# Project2SCH.net
KiCad netlist of a schematic drawn in Altium Designer
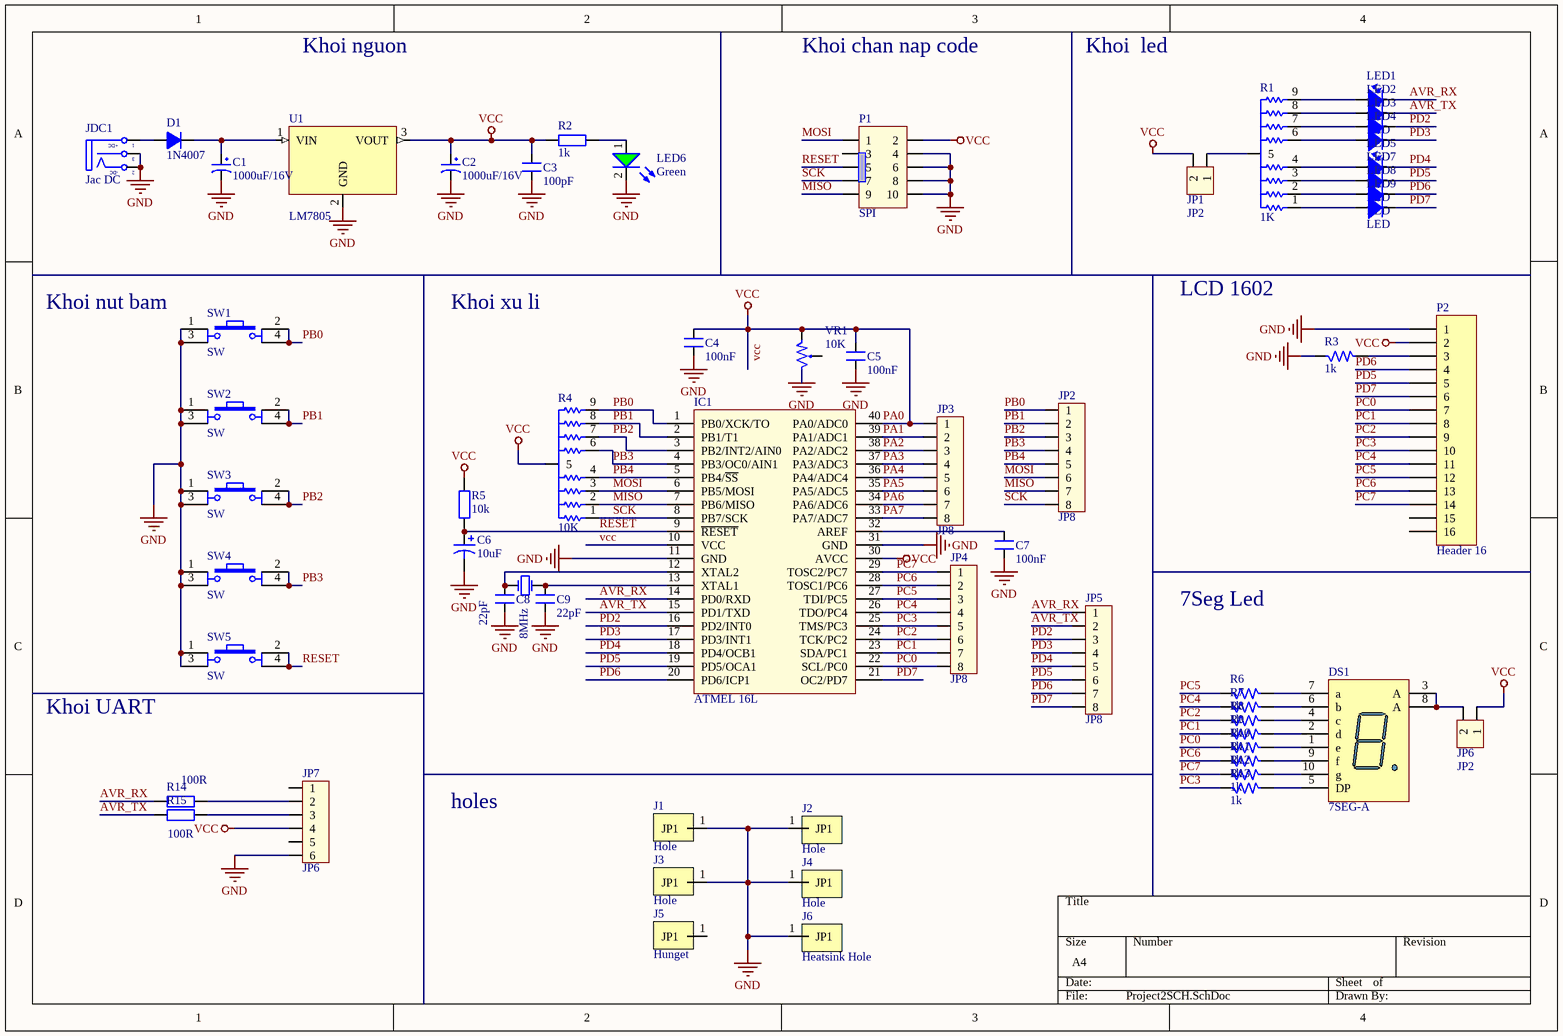
[diagram p0: Project2SCH.SchDoc]

(export (version "E")
  (design (tool "Eeschema 10.0.6"))
  (components
    (comp (ref "C1")
      (value "1000uF/16V")
      (footprint "CP1.5/3.4")
      (description "Cap 1000uF/16V - 220uF/50V")
      (libsource (lib "Cty1") (part "CP4"))
    )
    (comp (ref "C2")
      (value "1000uF/16V")
      (footprint "CP1.5/3.4")
      (description "Cap 1000uF/16V - 220uF/50V")
      (libsource (lib "Cty1") (part "CP4"))
    )
    (comp (ref "C3")
      (value "100pF")
      (footprint "CN1")
      (description "Cap np  1pF - 472pF")
      (libsource (lib "SCH_Lib_Devzone") (part "CN1"))
    )
    (comp (ref "C4")
      (value "100nF")
      (footprint "CN1")
      (description "Cap np  1pF - 472pF")
      (libsource (lib "Cty1") (part "CN1"))
    )
    (comp (ref "C5")
      (value "100nF")
      (footprint "CN1")
      (description "Cap np  1pF - 472pF")
      (libsource (lib "Cty1") (part "CN1"))
    )
    (comp (ref "C6")
      (value "10uF")
      (footprint "C5mm")
      (description "Polarized Capacitor (Axial)")
      (fields (field (name "PUBLISHER") "Altium Limited"))
      (libsource (lib "Schematic") (part "Cap Pol 5mm"))
    )
    (comp (ref "C7")
      (value "100nF")
      (footprint "CN1")
      (description "Cap np  1pF - 472pF")
      (libsource (lib "SCH_Lib_Devzone") (part "CN1"))
    )
    (comp (ref "C8")
      (value "22pF")
      (footprint "CN1")
      (description "Cap np  1pF - 472pF")
      (libsource (lib "Cty1") (part "CN1"))
    )
    (comp (ref "C9")
      (value "22pF")
      (footprint "CN1")
      (description "Cap np  1pF - 472pF")
      (libsource (lib "Cty1") (part "CN1"))
    )
    (comp (ref "D1")
      (value "1N4007")
      (footprint "D2A")
      (description "Diode 1A")
      (libsource (lib "Cty1") (part "D1A"))
    )
    (comp (ref "DS1")
      (value "7SEG-A")
      (footprint "LED7SEG")
      (description "14.2 mm General Purpose Blue 7-Segment Display: CA, RH DP, Gray Surface")
      (fields (field (name "PUBLISHER") "Altium Limited"))
      (libsource (lib "Schematic") (part "LED7SEG-A"))
    )
    (comp (ref "IC1")
      (value "ATMEL 16L")
      (footprint "DIP40/W0.6")
      (description "8-Bit AVR Microcontroller with 16K Bytes of In-System Programmable Flash Memory")
      (libsource (lib "SCH_Lib_Devzone") (part "Atmega16L"))
    )
    (comp (ref "J1")
      (value "Hole")
      (footprint "JP1")
      (description "JP1")
      (libsource (lib "SCH_Lib_Devzone") (part "JP1"))
    )
    (comp (ref "J2") (value "Hole") (footprint "JP1") (description "JP1") (libsource (lib "") (part "JP1_1")))
    (comp (ref "J3")
      (value "Hole")
      (footprint "JP1")
      (description "JP1")
      (libsource (lib "SCH_Lib_Devzone") (part "JP1"))
    )
    (comp (ref "J4") (value "Hole") (footprint "JP1") (description "JP1") (libsource (lib "") (part "JP1_1")))
    (comp (ref "J5")
      (value "Hunget")
      (footprint "JP1")
      (description "JP1")
      (libsource (lib "SCH_Lib_Devzone") (part "JP1"))
    )
    (comp (ref "J6")
      (value "Heatsink Hole")
      (footprint "JP1")
      (description "JP1")
      (libsource (lib "") (part "JP1_1"))
    )
    (comp (ref "JDC1")
      (value "Jac DC")
      (footprint "DC-IN")
      (description "Jac DC input")
      (libsource (lib "Cty1") (part "DCIN"))
    )
    (comp (ref "JP1")
      (value "JP2")
      (footprint "CON2")
      (description "Connector 2")
      (libsource (lib "SCH_MyLib_0") (part "Con2"))
    )
    (comp (ref "JP2")
      (value "JP8")
      (footprint "CON8")
      (description "Connector 8")
      (libsource (lib "VioletofSun") (part "Con8"))
    )
    (comp (ref "JP3")
      (value "JP8")
      (footprint "CON8")
      (description "Connector 8")
      (libsource (lib "VioletofSun") (part "Con8"))
    )
    (comp (ref "JP4")
      (value "JP8")
      (footprint "CON8")
      (description "Connector 8")
      (libsource (lib "VioletofSun") (part "Con8"))
    )
    (comp (ref "JP5")
      (value "JP8")
      (footprint "CON8")
      (description "Connector 8")
      (libsource (lib "VioletofSun") (part "Con8"))
    )
    (comp (ref "JP6")
      (value "JP2")
      (footprint "CON2")
      (description "Connector 2")
      (libsource (lib "SCH_MyLib_0") (part "Con2"))
    )
    (comp (ref "JP7")
      (value "JP6")
      (footprint "CON6")
      (description "Connector 6")
      (libsource (lib "syhaunguyen") (part "Con6"))
    )
    (comp (ref "LED1")
      (value "LED")
      (footprint "LED-V")
      (description "LED Single colour Green and Red")
      (libsource (lib "SCH_Lib_Devzone") (part "LED"))
    )
    (comp (ref "LED2")
      (value "LED")
      (footprint "LED-V")
      (description "LED Single colour Green and Red")
      (libsource (lib "SCH_Lib_Devzone") (part "LED"))
    )
    (comp (ref "LED3")
      (value "LED")
      (footprint "LED-V")
      (description "LED Single colour Green and Red")
      (libsource (lib "SCH_Lib_Devzone") (part "LED"))
    )
    (comp (ref "LED4")
      (value "LED")
      (footprint "LED-V")
      (description "LED Single colour Green and Red")
      (libsource (lib "SCH_Lib_Devzone") (part "LED"))
    )
    (comp (ref "LED5")
      (value "LED")
      (footprint "LED-V")
      (description "LED Single colour Green and Red")
      (libsource (lib "SCH_Lib_Devzone") (part "LED"))
    )
    (comp (ref "LED6")
      (value "Green")
      (footprint "LED5G")
      (description "LED Green 5mm")
      (fields (field (name "Comment") "LED_G_5"))
      (libsource (lib "SCH_MyLib_0") (part "LED_GREEN_5MM"))
    )
    (comp (ref "LED7")
      (value "LED")
      (footprint "LED-V")
      (description "LED Single colour Green and Red")
      (libsource (lib "SCH_Lib_Devzone") (part "LED"))
    )
    (comp (ref "LED8")
      (value "LED")
      (footprint "LED-V")
      (description "LED Single colour Green and Red")
      (libsource (lib "SCH_Lib_Devzone") (part "LED"))
    )
    (comp (ref "LED9")
      (value "LED")
      (footprint "LED-V")
      (description "LED Single colour Green and Red")
      (libsource (lib "SCH_Lib_Devzone") (part "LED"))
    )
    (comp (ref "P1")
      (value "SPI")
      (footprint "IDE_2X5")
      (description "Header 5x2")
      (libsource (lib "SCH_Lib_Devzone") (part "IDE 5x2"))
    )
    (comp (ref "P2")
      (value "Header 16")
      (footprint "HDR1X16")
      (description "Header, 16-Pin")
      (fields (field (name "PUBLISHER") "Altium Limited"))
      (libsource (lib "Devzone_SCHLib") (part "Header 16"))
    )
    (comp (ref "R1")
      (value "1K")
      (footprint "VioletofSun:RN8")
      (description "Resistor Pack 4x2")
      (libsource (lib "VioletofSun") (part "RKC8LD"))
    )
    (comp (ref "R2")
      (value "1k")
      (footprint "R1/4W")
      (description "Resistor 1/4W")
      (libsource (lib "SCH_Lib_Devzone") (part "R1/4W"))
    )
    (comp (ref "R3")
      (value "1k")
      (footprint "R1/6W")
      (description "Resistor 1/4W")
      (libsource (lib "Cty1") (part "Res"))
    )
    (comp (ref "R4")
      (value "10K")
      (footprint "VioletofSun:RN8")
      (description "Resistor Pack 4x2")
      (libsource (lib "VioletofSun") (part "RKC8LD"))
    )
    (comp (ref "R5")
      (value "10k")
      (footprint "R1/4W")
      (description "Resistor 1/4W")
      (libsource (lib "Devzone_SCHLib") (part "R1/4W"))
    )
    (comp (ref "R6")
      (value "1k")
      (footprint "R1/6W")
      (description "Resistor 1/4W")
      (libsource (lib "Cty1") (part "Res"))
    )
    (comp (ref "R7")
      (value "1k")
      (footprint "R1/6W")
      (description "Resistor 1/4W")
      (libsource (lib "Cty1") (part "Res"))
    )
    (comp (ref "R8")
      (value "1k")
      (footprint "R1/6W")
      (description "Resistor 1/4W")
      (libsource (lib "Cty1") (part "Res"))
    )
    (comp (ref "R9")
      (value "1k")
      (footprint "R1/6W")
      (description "Resistor 1/4W")
      (libsource (lib "Cty1") (part "Res"))
    )
    (comp (ref "R10")
      (value "1k")
      (footprint "R1/6W")
      (description "Resistor 1/4W")
      (libsource (lib "Cty1") (part "Res"))
    )
    (comp (ref "R11")
      (value "1k")
      (footprint "R1/6W")
      (description "Resistor 1/4W")
      (libsource (lib "Cty1") (part "Res"))
    )
    (comp (ref "R12")
      (value "1k")
      (footprint "R1/6W")
      (description "Resistor 1/4W")
      (libsource (lib "Cty1") (part "Res"))
    )
    (comp (ref "R13")
      (value "1k")
      (footprint "R1/6W")
      (description "Resistor 1/4W")
      (libsource (lib "Cty1") (part "Res"))
    )
    (comp (ref "R14")
      (value "100R")
      (footprint "R1/4W")
      (description "Resistor 1/4W")
      (libsource (lib "Devzone_SCHLib") (part "R1/4W"))
    )
    (comp (ref "R15")
      (value "100R")
      (footprint "R1/4W")
      (description "Resistor 1/4W")
      (libsource (lib "Devzone_SCHLib") (part "R1/4W"))
    )
    (comp (ref "SW1")
      (value "SW")
      (footprint "SW-4P-S")
      (description "Switch button 4 pin")
      (libsource (lib "Cty1") (part "SW4"))
    )
    (comp (ref "SW2")
      (value "SW")
      (footprint "SW-4P-S")
      (description "Switch button 4 pin")
      (libsource (lib "Cty1") (part "SW4"))
    )
    (comp (ref "SW3")
      (value "SW")
      (footprint "SW-4P-S")
      (description "Switch button 4 pin")
      (libsource (lib "Cty1") (part "SW4"))
    )
    (comp (ref "SW4")
      (value "SW")
      (footprint "SW-4P-S")
      (description "Switch button 4 pin")
      (libsource (lib "Cty1") (part "SW4"))
    )
    (comp (ref "SW5")
      (value "SW")
      (footprint "SW-4P-S")
      (description "Switch button 4 pin")
      (libsource (lib "Cty1") (part "SW4"))
    )
    (comp (ref "U1")
      (value "LM7805")
      (footprint "QTO-220H3")
      (description "TO-220")
      (libsource (lib "Cty1") (part "LM7805"))
    )
    (comp (ref "VR1")
      (value "10K")
      (footprint "VioletofSun:VR")
      (description "Var Resistor")
      (libsource (lib "VioletofSun") (part "VR1"))
    )
    (comp (ref "Y1")
      (value "8MHz")
      (footprint "XT2")
      (description "Crystal Oscillator")
      (fields (field (name "PUBLISHER") "Altium Limited"))
      (libsource (lib "Devzone_SCHLib") (part "Crystal"))
    )
  )
  (nets
    (net (code "1") (name "/AVR_RX") (class "Default")
      (node (ref "IC1") (pin "14") (pinfunction "PD0/RXD_14") (pintype "passive"))
      (node (ref "JP5") (pin "1") (pinfunction "1_1") (pintype "passive"))
      (node (ref "LED1") (pin "2") (pinfunction "2_2") (pintype "passive"))
      (node (ref "R14") (pin "1") (pinfunction "1_1") (pintype "passive"))
    )
    (net (code "2") (name "/AVR_TX") (class "Default")
      (node (ref "IC1") (pin "15") (pinfunction "PD1/TXD_15") (pintype "passive"))
      (node (ref "JP5") (pin "2") (pinfunction "2_2") (pintype "passive"))
      (node (ref "LED2") (pin "2") (pinfunction "2_2") (pintype "passive"))
      (node (ref "R15") (pin "1") (pinfunction "1_1") (pintype "passive"))
    )
    (net (code "3") (name "/MISO") (class "Default")
      (node (ref "IC1") (pin "7") (pinfunction "PB6/MISO_7") (pintype "passive"))
      (node (ref "JP2") (pin "7") (pinfunction "7_7") (pintype "passive"))
      (node (ref "P1") (pin "9") (pinfunction "9_9") (pintype "passive"))
      (node (ref "R4") (pin "2") (pinfunction "2_2") (pintype "passive"))
    )
    (net (code "4") (name "/MOSI") (class "Default")
      (node (ref "IC1") (pin "6") (pinfunction "PB5/MOSI_6") (pintype "passive"))
      (node (ref "JP2") (pin "6") (pinfunction "6_6") (pintype "passive"))
      (node (ref "P1") (pin "1") (pinfunction "1_1") (pintype "passive"))
      (node (ref "R4") (pin "3") (pinfunction "3_3") (pintype "passive"))
    )
    (net (code "5") (name "/PA1") (class "Default")
      (node (ref "IC1") (pin "39") (pinfunction "PA1/ADC1_39") (pintype "passive"))
      (node (ref "JP3") (pin "2") (pinfunction "2_2") (pintype "passive"))
    )
    (net (code "6") (name "/PA2") (class "Default")
      (node (ref "IC1") (pin "38") (pinfunction "PA2/ADC2_38") (pintype "passive"))
      (node (ref "JP3") (pin "3") (pinfunction "3_3") (pintype "passive"))
    )
    (net (code "7") (name "/PA3") (class "Default")
      (node (ref "IC1") (pin "37") (pinfunction "PA3/ADC3_37") (pintype "passive"))
      (node (ref "JP3") (pin "4") (pinfunction "4_4") (pintype "passive"))
    )
    (net (code "8") (name "/PA4") (class "Default")
      (node (ref "IC1") (pin "36") (pinfunction "PA4/ADC4_36") (pintype "passive"))
      (node (ref "JP3") (pin "5") (pinfunction "5_5") (pintype "passive"))
    )
    (net (code "9") (name "/PA5") (class "Default")
      (node (ref "IC1") (pin "35") (pinfunction "PA5/ADC5_35") (pintype "passive"))
      (node (ref "JP3") (pin "6") (pinfunction "6_6") (pintype "passive"))
    )
    (net (code "10") (name "/PA6") (class "Default")
      (node (ref "IC1") (pin "34") (pinfunction "PA6/ADC6_34") (pintype "passive"))
      (node (ref "JP3") (pin "7") (pinfunction "7_7") (pintype "passive"))
    )
    (net (code "11") (name "/PA7") (class "Default")
      (node (ref "IC1") (pin "33") (pinfunction "PA7/ADC7_33") (pintype "passive"))
      (node (ref "JP3") (pin "8") (pinfunction "8_8") (pintype "passive"))
    )
    (net (code "12") (name "/PB0") (class "Default")
      (node (ref "IC1") (pin "1") (pinfunction "PB0/XCK/TO_1") (pintype "passive"))
      (node (ref "JP2") (pin "1") (pinfunction "1_1") (pintype "passive"))
      (node (ref "R4") (pin "9") (pinfunction "9_9") (pintype "passive"))
      (node (ref "SW1") (pin "2") (pintype "passive"))
      (node (ref "SW1") (pin "4") (pintype "passive"))
    )
    (net (code "13") (name "/PB1") (class "Default")
      (node (ref "IC1") (pin "2") (pinfunction "PB1/T1_2") (pintype "passive"))
      (node (ref "JP2") (pin "2") (pinfunction "2_2") (pintype "passive"))
      (node (ref "R4") (pin "8") (pinfunction "8_8") (pintype "passive"))
      (node (ref "SW2") (pin "2") (pintype "passive"))
      (node (ref "SW2") (pin "4") (pintype "passive"))
    )
    (net (code "14") (name "/PB2") (class "Default")
      (node (ref "IC1") (pin "3") (pinfunction "PB2/INT2/AIN0_3") (pintype "passive"))
      (node (ref "JP2") (pin "3") (pinfunction "3_3") (pintype "passive"))
      (node (ref "R4") (pin "7") (pinfunction "7_7") (pintype "passive"))
      (node (ref "SW3") (pin "2") (pintype "passive"))
      (node (ref "SW3") (pin "4") (pintype "passive"))
    )
    (net (code "15") (name "/PB3") (class "Default")
      (node (ref "IC1") (pin "4") (pinfunction "PB3/OC0/AIN1_4") (pintype "passive"))
      (node (ref "JP2") (pin "4") (pinfunction "4_4") (pintype "passive"))
      (node (ref "R4") (pin "6") (pinfunction "6_6") (pintype "passive"))
      (node (ref "SW4") (pin "2") (pintype "passive"))
      (node (ref "SW4") (pin "4") (pintype "passive"))
    )
    (net (code "16") (name "/PB4") (class "Default")
      (node (ref "IC1") (pin "5") (pinfunction "PB4/~{SS}_5") (pintype "passive"))
      (node (ref "JP2") (pin "5") (pinfunction "5_5") (pintype "passive"))
      (node (ref "R4") (pin "4") (pinfunction "4_4") (pintype "passive"))
    )
    (net (code "17") (name "/PC0") (class "Default")
      (node (ref "IC1") (pin "22") (pinfunction "SCL/PC0_22") (pintype "passive"))
      (node (ref "JP4") (pin "8") (pinfunction "8_8") (pintype "passive"))
      (node (ref "P2") (pin "7") (pinfunction "7_7") (pintype "passive"))
      (node (ref "R10") (pin "1") (pinfunction "1_1") (pintype "passive"))
    )
    (net (code "18") (name "/PC1") (class "Default")
      (node (ref "IC1") (pin "23") (pinfunction "SDA/PC1_23") (pintype "passive"))
      (node (ref "JP4") (pin "7") (pinfunction "7_7") (pintype "passive"))
      (node (ref "P2") (pin "8") (pinfunction "8_8") (pintype "passive"))
      (node (ref "R9") (pin "1") (pinfunction "1_1") (pintype "passive"))
    )
    (net (code "19") (name "/PC2") (class "Default")
      (node (ref "IC1") (pin "24") (pinfunction "TCK/PC2_24") (pintype "passive"))
      (node (ref "JP4") (pin "6") (pinfunction "6_6") (pintype "passive"))
      (node (ref "P2") (pin "9") (pinfunction "9_9") (pintype "passive"))
      (node (ref "R8") (pin "1") (pinfunction "1_1") (pintype "passive"))
    )
    (net (code "20") (name "/PC3") (class "Default")
      (node (ref "IC1") (pin "25") (pinfunction "TMS/PC3_25") (pintype "passive"))
      (node (ref "JP4") (pin "5") (pinfunction "5_5") (pintype "passive"))
      (node (ref "P2") (pin "10") (pinfunction "10_10") (pintype "passive"))
      (node (ref "R13") (pin "1") (pinfunction "1_1") (pintype "passive"))
    )
    (net (code "21") (name "/PC4") (class "Default")
      (node (ref "IC1") (pin "26") (pinfunction "TDO/PC4_26") (pintype "passive"))
      (node (ref "JP4") (pin "4") (pinfunction "4_4") (pintype "passive"))
      (node (ref "P2") (pin "11") (pinfunction "11_11") (pintype "passive"))
      (node (ref "R7") (pin "1") (pinfunction "1_1") (pintype "passive"))
    )
    (net (code "22") (name "/PC5") (class "Default")
      (node (ref "IC1") (pin "27") (pinfunction "TDI/PC5_27") (pintype "passive"))
      (node (ref "JP4") (pin "3") (pinfunction "3_3") (pintype "passive"))
      (node (ref "P2") (pin "12") (pinfunction "12_12") (pintype "passive"))
      (node (ref "R6") (pin "1") (pinfunction "1_1") (pintype "passive"))
    )
    (net (code "23") (name "/PC6") (class "Default")
      (node (ref "IC1") (pin "28") (pinfunction "TOSC1/PC6_28") (pintype "passive"))
      (node (ref "JP4") (pin "2") (pinfunction "2_2") (pintype "passive"))
      (node (ref "P2") (pin "13") (pinfunction "13_13") (pintype "passive"))
      (node (ref "R11") (pin "1") (pinfunction "1_1") (pintype "passive"))
    )
    (net (code "24") (name "/PC7") (class "Default")
      (node (ref "IC1") (pin "29") (pinfunction "TOSC2/PC7_29") (pintype "passive"))
      (node (ref "JP4") (pin "1") (pinfunction "1_1") (pintype "passive"))
      (node (ref "P2") (pin "14") (pinfunction "14_14") (pintype "passive"))
      (node (ref "R12") (pin "1") (pinfunction "1_1") (pintype "passive"))
    )
    (net (code "25") (name "/PD2") (class "Default")
      (node (ref "IC1") (pin "16") (pinfunction "PD2/INT0_16") (pintype "passive"))
      (node (ref "JP5") (pin "3") (pinfunction "3_3") (pintype "passive"))
      (node (ref "LED3") (pin "2") (pinfunction "2_2") (pintype "passive"))
    )
    (net (code "26") (name "/PD3") (class "Default")
      (node (ref "IC1") (pin "17") (pinfunction "PD3/INT1_17") (pintype "passive"))
      (node (ref "JP5") (pin "4") (pinfunction "4_4") (pintype "passive"))
      (node (ref "LED4") (pin "2") (pinfunction "2_2") (pintype "passive"))
    )
    (net (code "27") (name "/PD4") (class "Default")
      (node (ref "IC1") (pin "18") (pinfunction "PD4/OCB1_18") (pintype "passive"))
      (node (ref "JP5") (pin "5") (pinfunction "5_5") (pintype "passive"))
      (node (ref "LED5") (pin "2") (pinfunction "2_2") (pintype "passive"))
    )
    (net (code "28") (name "/PD5") (class "Default")
      (node (ref "IC1") (pin "19") (pinfunction "PD5/OCA1_19") (pintype "passive"))
      (node (ref "JP5") (pin "6") (pinfunction "6_6") (pintype "passive"))
      (node (ref "LED7") (pin "2") (pinfunction "2_2") (pintype "passive"))
      (node (ref "P2") (pin "5") (pinfunction "5_5") (pintype "passive"))
    )
    (net (code "29") (name "/PD6") (class "Default")
      (node (ref "IC1") (pin "20") (pinfunction "PD6/ICP1_20") (pintype "passive"))
      (node (ref "JP5") (pin "7") (pinfunction "7_7") (pintype "passive"))
      (node (ref "LED8") (pin "2") (pinfunction "2_2") (pintype "passive"))
      (node (ref "P2") (pin "4") (pinfunction "4_4") (pintype "passive"))
    )
    (net (code "30") (name "/PD7") (class "Default")
      (node (ref "IC1") (pin "21") (pinfunction "OC2/PD7_21") (pintype "passive"))
      (node (ref "JP5") (pin "8") (pinfunction "8_8") (pintype "passive"))
      (node (ref "LED9") (pin "2") (pinfunction "2_2") (pintype "passive"))
      (node (ref "P2") (pin "6") (pinfunction "6_6") (pintype "passive"))
    )
    (net (code "31") (name "/RESET") (class "Default")
      (node (ref "C6") (pin "1") (pinfunction "1_1") (pintype "passive"))
      (node (ref "IC1") (pin "9") (pinfunction "~{RESET}_9") (pintype "passive"))
      (node (ref "P1") (pin "5") (pinfunction "5_5") (pintype "passive"))
      (node (ref "R5") (pin "1") (pinfunction "1_1") (pintype "passive"))
      (node (ref "SW5") (pin "2") (pintype "passive"))
      (node (ref "SW5") (pin "4") (pintype "passive"))
    )
    (net (code "32") (name "/SCK") (class "Default")
      (node (ref "IC1") (pin "8") (pinfunction "PB7/SCK_8") (pintype "passive"))
      (node (ref "JP2") (pin "8") (pinfunction "8_8") (pintype "passive"))
      (node (ref "P1") (pin "7") (pinfunction "7_7") (pintype "passive"))
      (node (ref "R4") (pin "1") (pinfunction "1_1") (pintype "passive"))
    )
    (net (code "33") (name "GND") (class "Default")
      (node (ref "C1") (pin "2") (pinfunction "2_2") (pintype "passive"))
      (node (ref "C2") (pin "2") (pinfunction "2_2") (pintype "passive"))
      (node (ref "C3") (pin "1") (pinfunction "1_1") (pintype "passive"))
      (node (ref "C4") (pin "1") (pinfunction "1_1") (pintype "passive"))
      (node (ref "C5") (pin "1") (pinfunction "1_1") (pintype "passive"))
      (node (ref "C6") (pin "2") (pinfunction "2_2") (pintype "passive"))
      (node (ref "C7") (pin "1") (pinfunction "1_1") (pintype "passive"))
      (node (ref "C8") (pin "1") (pinfunction "1_1") (pintype "passive"))
      (node (ref "C9") (pin "1") (pinfunction "1_1") (pintype "passive"))
      (node (ref "IC1") (pin "11") (pinfunction "GND_11") (pintype "passive"))
      (node (ref "IC1") (pin "31") (pinfunction "GND_31") (pintype "passive"))
      (node (ref "J1") (pin "1") (pinfunction "JP1_1") (pintype "passive"))
      (node (ref "J2") (pin "1") (pinfunction "JP1_1") (pintype "passive"))
      (node (ref "J3") (pin "1") (pinfunction "JP1_1") (pintype "passive"))
      (node (ref "J4") (pin "1") (pinfunction "JP1_1") (pintype "passive"))
      (node (ref "J6") (pin "1") (pinfunction "JP1_1") (pintype "passive"))
      (node (ref "JDC1") (pin "2") (pinfunction "TN_2") (pintype "passive"))
      (node (ref "JDC1") (pin "3") (pinfunction "S_3") (pintype "power_in"))
      (node (ref "JP7") (pin "6") (pinfunction "6_6") (pintype "passive"))
      (node (ref "LED6") (pin "2") (pinfunction "K_2") (pintype "passive"))
      (node (ref "P1") (pin "10") (pinfunction "10_10") (pintype "passive"))
      (node (ref "P1") (pin "4") (pinfunction "4_4") (pintype "passive"))
      (node (ref "P1") (pin "6") (pinfunction "6_6") (pintype "passive"))
      (node (ref "P1") (pin "8") (pinfunction "8_8") (pintype "passive"))
      (node (ref "P2") (pin "1") (pinfunction "1_1") (pintype "passive"))
      (node (ref "R3") (pin "1") (pinfunction "1_1") (pintype "passive"))
      (node (ref "SW1") (pin "1") (pintype "passive"))
      (node (ref "SW1") (pin "3") (pintype "passive"))
      (node (ref "SW2") (pin "1") (pintype "passive"))
      (node (ref "SW2") (pin "3") (pintype "passive"))
      (node (ref "SW3") (pin "1") (pintype "passive"))
      (node (ref "SW3") (pin "3") (pintype "passive"))
      (node (ref "SW4") (pin "1") (pintype "passive"))
      (node (ref "SW4") (pin "3") (pintype "passive"))
      (node (ref "SW5") (pin "1") (pintype "passive"))
      (node (ref "SW5") (pin "3") (pintype "passive"))
      (node (ref "U1") (pin "2") (pinfunction "GND_2") (pintype "power_in"))
      (node (ref "VR1") (pin "3") (pinfunction "3_3") (pintype "passive"))
    )
    (net (code "34") (name "Net-(D1-A)") (class "Default")
      (node (ref "D1") (pin "1") (pinfunction "A_1") (pintype "passive"))
      (node (ref "JDC1") (pin "1") (pinfunction "T_1") (pintype "passive"))
    )
    (net (code "35") (name "Net-(D1-K)") (class "Default")
      (node (ref "C1") (pin "1") (pinfunction "1_1") (pintype "passive"))
      (node (ref "D1") (pin "2") (pinfunction "K_2") (pintype "passive"))
      (node (ref "U1") (pin "1") (pinfunction "VIN_1") (pintype "input"))
    )
    (net (code "36") (name "Net-(DS1-A-Pad3)") (class "Default")
      (node (ref "DS1") (pin "3") (pinfunction "A_3") (pintype "passive"))
      (node (ref "DS1") (pin "8") (pinfunction "A_8") (pintype "passive"))
      (node (ref "JP6") (pin "2") (pinfunction "2_2") (pintype "passive"))
    )
    (net (code "37") (name "Net-(DS1-DP)") (class "Default")
      (node (ref "DS1") (pin "5") (pinfunction "DP_5") (pintype "passive"))
      (node (ref "R13") (pin "2") (pinfunction "2_2") (pintype "passive"))
    )
    (net (code "38") (name "Net-(DS1-a)") (class "Default")
      (node (ref "DS1") (pin "7") (pinfunction "a_7") (pintype "passive"))
      (node (ref "R6") (pin "2") (pinfunction "2_2") (pintype "passive"))
    )
    (net (code "39") (name "Net-(DS1-b)") (class "Default")
      (node (ref "DS1") (pin "6") (pinfunction "b_6") (pintype "passive"))
      (node (ref "R7") (pin "2") (pinfunction "2_2") (pintype "passive"))
    )
    (net (code "40") (name "Net-(DS1-c)") (class "Default")
      (node (ref "DS1") (pin "4") (pinfunction "c_4") (pintype "passive"))
      (node (ref "R8") (pin "2") (pinfunction "2_2") (pintype "passive"))
    )
    (net (code "41") (name "Net-(DS1-d)") (class "Default")
      (node (ref "DS1") (pin "2") (pinfunction "d_2") (pintype "passive"))
      (node (ref "R9") (pin "2") (pinfunction "2_2") (pintype "passive"))
    )
    (net (code "42") (name "Net-(DS1-e)") (class "Default")
      (node (ref "DS1") (pin "1") (pinfunction "e_1") (pintype "passive"))
      (node (ref "R10") (pin "2") (pinfunction "2_2") (pintype "passive"))
    )
    (net (code "43") (name "Net-(DS1-f)") (class "Default")
      (node (ref "DS1") (pin "9") (pinfunction "f_9") (pintype "passive"))
      (node (ref "R11") (pin "2") (pinfunction "2_2") (pintype "passive"))
    )
    (net (code "44") (name "Net-(DS1-g)") (class "Default")
      (node (ref "DS1") (pin "10") (pinfunction "g_10") (pintype "passive"))
      (node (ref "R12") (pin "2") (pinfunction "2_2") (pintype "passive"))
    )
    (net (code "45") (name "Net-(IC1-AREF)") (class "Default")
      (node (ref "C7") (pin "2") (pinfunction "2_2") (pintype "passive"))
      (node (ref "IC1") (pin "32") (pinfunction "AREF_32") (pintype "passive"))
    )
    (net (code "46") (name "Net-(IC1-XTAL1)") (class "Default")
      (node (ref "C9") (pin "2") (pinfunction "2_2") (pintype "passive"))
      (node (ref "IC1") (pin "13") (pinfunction "XTAL1_13") (pintype "passive"))
      (node (ref "Y1") (pin "2") (pinfunction "OSC2_2") (pintype "passive"))
    )
    (net (code "47") (name "Net-(IC1-XTAL2)") (class "Default")
      (node (ref "C8") (pin "2") (pinfunction "2_2") (pintype "passive"))
      (node (ref "IC1") (pin "12") (pinfunction "XTAL2_12") (pintype "passive"))
      (node (ref "Y1") (pin "1") (pinfunction "OSC1_1") (pintype "passive"))
    )
    (net (code "48") (name "Net-(JP1-Pad1)") (class "Default")
      (node (ref "JP1") (pin "1") (pinfunction "1_1") (pintype "passive"))
      (node (ref "R1") (pin "5") (pinfunction "5_5") (pintype "passive"))
    )
    (net (code "49") (name "Net-(JP7-Pad2)") (class "Default")
      (node (ref "JP7") (pin "2") (pinfunction "2_2") (pintype "passive"))
      (node (ref "R14") (pin "2") (pinfunction "2_2") (pintype "passive"))
    )
    (net (code "50") (name "Net-(JP7-Pad3)") (class "Default")
      (node (ref "JP7") (pin "3") (pinfunction "3_3") (pintype "passive"))
      (node (ref "R15") (pin "2") (pinfunction "2_2") (pintype "passive"))
    )
    (net (code "51") (name "Net-(LED1-Pad1)") (class "Default")
      (node (ref "LED1") (pin "1") (pinfunction "1_1") (pintype "passive"))
      (node (ref "R1") (pin "9") (pinfunction "9_9") (pintype "passive"))
    )
    (net (code "52") (name "Net-(LED2-Pad1)") (class "Default")
      (node (ref "LED2") (pin "1") (pinfunction "1_1") (pintype "passive"))
      (node (ref "R1") (pin "8") (pinfunction "8_8") (pintype "passive"))
    )
    (net (code "53") (name "Net-(LED3-Pad1)") (class "Default")
      (node (ref "LED3") (pin "1") (pinfunction "1_1") (pintype "passive"))
      (node (ref "R1") (pin "7") (pinfunction "7_7") (pintype "passive"))
    )
    (net (code "54") (name "Net-(LED4-Pad1)") (class "Default")
      (node (ref "LED4") (pin "1") (pinfunction "1_1") (pintype "passive"))
      (node (ref "R1") (pin "6") (pinfunction "6_6") (pintype "passive"))
    )
    (net (code "55") (name "Net-(LED5-Pad1)") (class "Default")
      (node (ref "LED5") (pin "1") (pinfunction "1_1") (pintype "passive"))
      (node (ref "R1") (pin "4") (pinfunction "4_4") (pintype "passive"))
    )
    (net (code "56") (name "Net-(LED6-A)") (class "Default")
      (node (ref "LED6") (pin "1") (pinfunction "A_1") (pintype "passive"))
      (node (ref "R2") (pin "2") (pinfunction "2_2") (pintype "passive"))
    )
    (net (code "57") (name "Net-(LED7-Pad1)") (class "Default")
      (node (ref "LED7") (pin "1") (pinfunction "1_1") (pintype "passive"))
      (node (ref "R1") (pin "3") (pinfunction "3_3") (pintype "passive"))
    )
    (net (code "58") (name "Net-(LED8-Pad1)") (class "Default")
      (node (ref "LED8") (pin "1") (pinfunction "1_1") (pintype "passive"))
      (node (ref "R1") (pin "2") (pinfunction "2_2") (pintype "passive"))
    )
    (net (code "59") (name "Net-(LED9-Pad1)") (class "Default")
      (node (ref "LED9") (pin "1") (pinfunction "1_1") (pintype "passive"))
      (node (ref "R1") (pin "1") (pinfunction "1_1") (pintype "passive"))
    )
    (net (code "60") (name "Net-(P2-Pad3)") (class "Default")
      (node (ref "P2") (pin "3") (pinfunction "3_3") (pintype "passive"))
      (node (ref "R3") (pin "2") (pinfunction "2_2") (pintype "passive"))
    )
    (net (code "61") (name "VCC") (class "Default")
      (node (ref "C2") (pin "1") (pinfunction "1_1") (pintype "passive"))
      (node (ref "C3") (pin "2") (pinfunction "2_2") (pintype "passive"))
      (node (ref "C4") (pin "2") (pinfunction "2_2") (pintype "passive"))
      (node (ref "C5") (pin "2") (pinfunction "2_2") (pintype "passive"))
      (node (ref "IC1") (pin "10") (pinfunction "VCC_10") (pintype "passive"))
      (node (ref "IC1") (pin "30") (pinfunction "AVCC_30") (pintype "passive"))
      (node (ref "IC1") (pin "40") (pinfunction "PA0/ADC0_40") (pintype "passive"))
      (node (ref "JP1") (pin "2") (pinfunction "2_2") (pintype "passive"))
      (node (ref "JP3") (pin "1") (pinfunction "1_1") (pintype "passive"))
      (node (ref "JP6") (pin "1") (pinfunction "1_1") (pintype "passive"))
      (node (ref "JP7") (pin "4") (pinfunction "4_4") (pintype "passive"))
      (node (ref "P1") (pin "2") (pinfunction "2_2") (pintype "passive"))
      (node (ref "P2") (pin "2") (pinfunction "2_2") (pintype "passive"))
      (node (ref "R2") (pin "1") (pinfunction "1_1") (pintype "passive"))
      (node (ref "R4") (pin "5") (pinfunction "5_5") (pintype "passive"))
      (node (ref "R5") (pin "2") (pinfunction "2_2") (pintype "passive"))
      (node (ref "U1") (pin "3") (pinfunction "VOUT_3") (pintype "output"))
      (node (ref "VR1") (pin "1") (pinfunction "1_1") (pintype "passive"))
    )
    (net (code "62") (name "unconnected-(J5-JP1-Pad1)") (class "Default")
      (node (ref "J5") (pin "1") (pinfunction "JP1_1") (pintype "passive"))
    )
    (net (code "63") (name "unconnected-(JP7-Pad1)") (class "Default")
      (node (ref "JP7") (pin "1") (pinfunction "1_1") (pintype "passive"))
    )
    (net (code "64") (name "unconnected-(JP7-Pad5)") (class "Default")
      (node (ref "JP7") (pin "5") (pinfunction "5_5") (pintype "passive"))
    )
    (net (code "65") (name "unconnected-(P1-Pad3)") (class "Default")
      (node (ref "P1") (pin "3") (pinfunction "3_3") (pintype "passive"))
    )
    (net (code "66") (name "unconnected-(P2-Pad15)") (class "Default")
      (node (ref "P2") (pin "15") (pinfunction "15_15") (pintype "passive"))
    )
    (net (code "67") (name "unconnected-(P2-Pad16)") (class "Default")
      (node (ref "P2") (pin "16") (pinfunction "16_16") (pintype "passive"))
    )
    (net (code "68") (name "unconnected-(VR1-Pad2)") (class "Default")
      (node (ref "VR1") (pin "2") (pinfunction "2_2") (pintype "passive"))
    )
  )
)
